# source_eagle.net
KiCad netlist of a schematic drawn in EAGLE
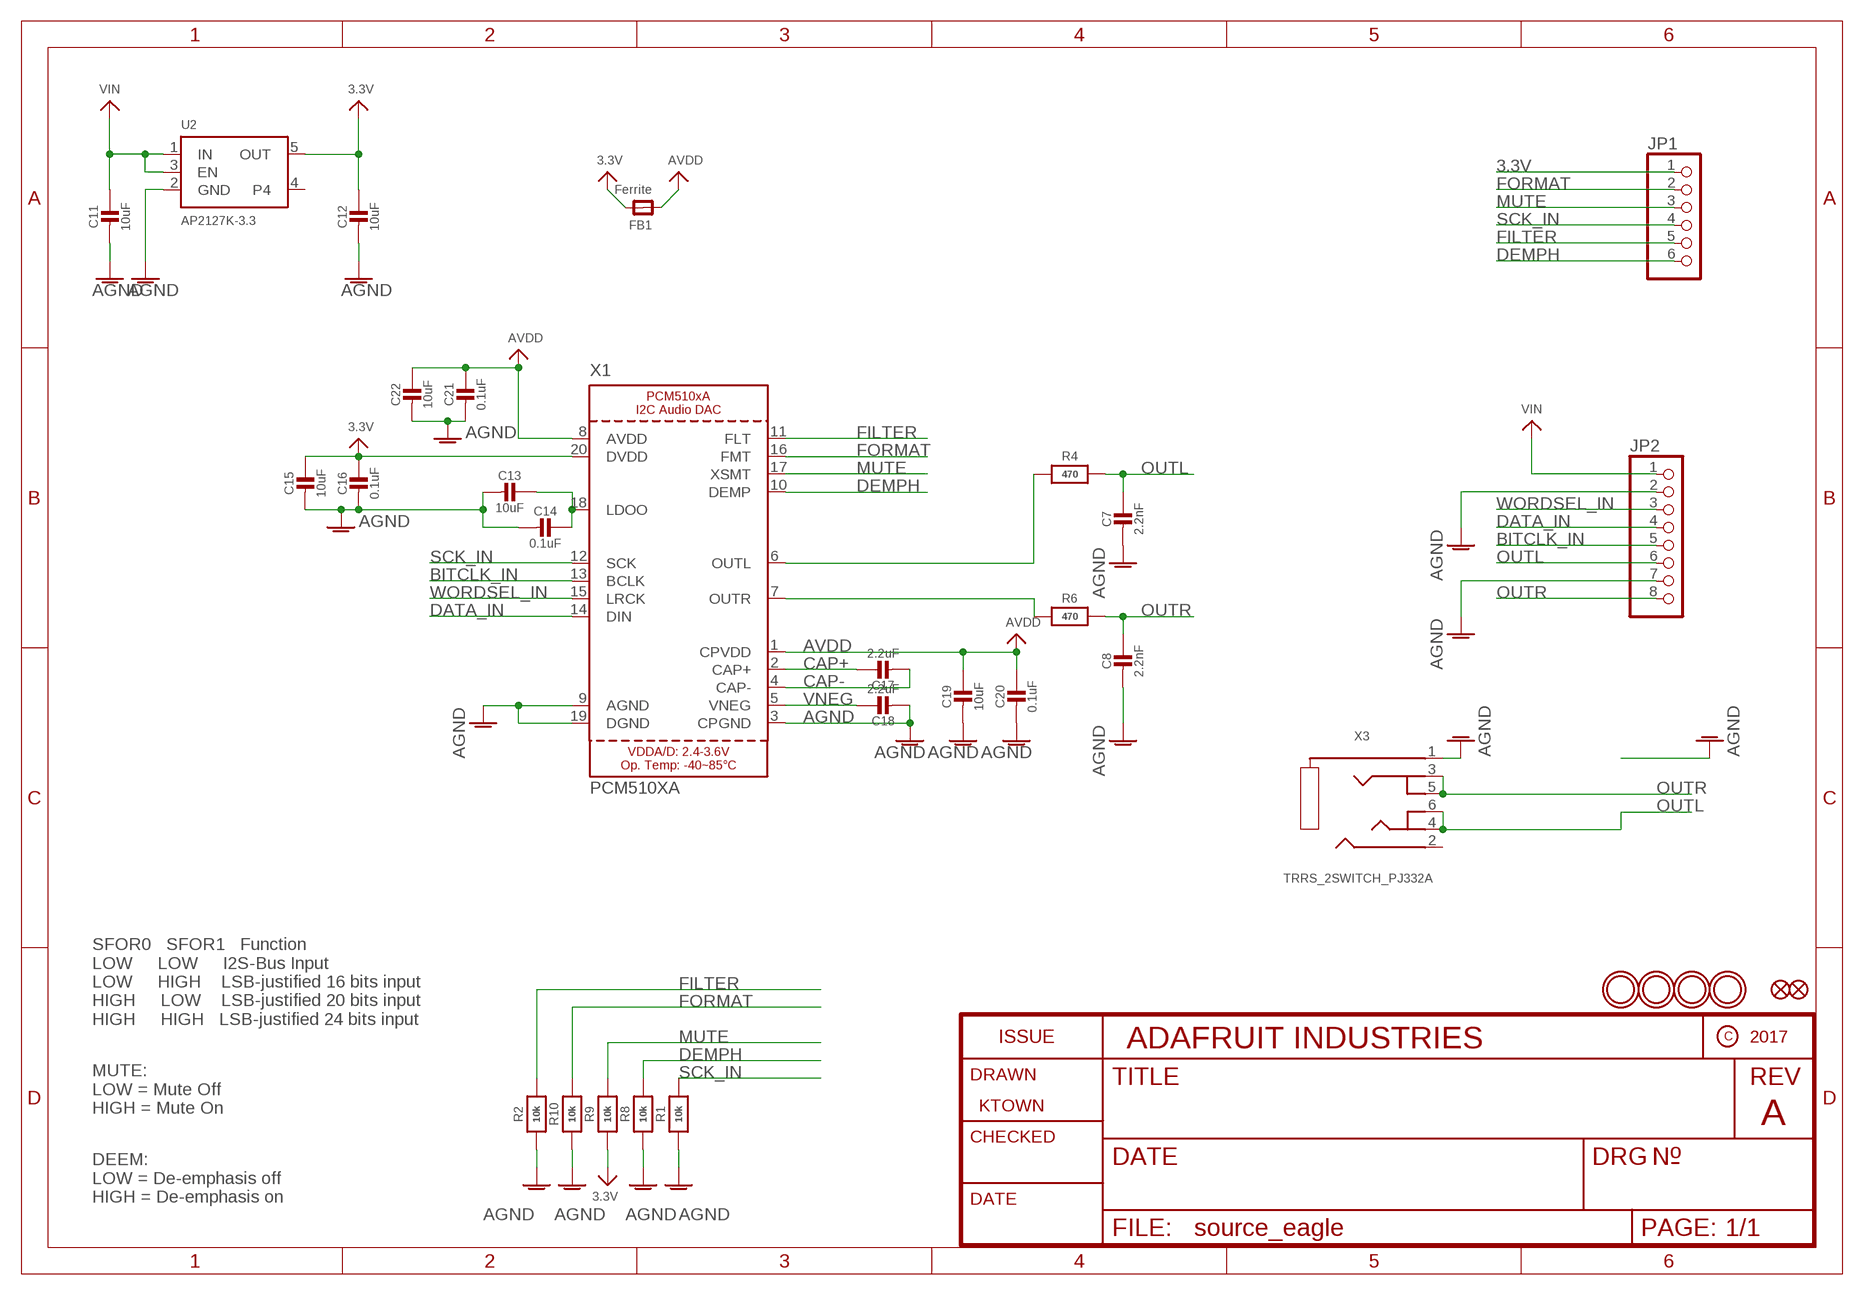
[diagram p0: schematic, sheet 1]

(export (version "E")
  (design (tool "Eeschema 10.0.6"))
  (components
    (comp (ref "C7")
      (value "2.2nF")
      (footprint "eagle-import:0603-NO")
      (libsource (lib "eagle-import") (part "CAP_CERAMIC0603_NO"))
    )
    (comp (ref "C8")
      (value "2.2nF")
      (footprint "eagle-import:0603-NO")
      (libsource (lib "eagle-import") (part "CAP_CERAMIC0603_NO"))
    )
    (comp (ref "C11")
      (value "10uF")
      (footprint "eagle-import:0805-NO")
      (libsource (lib "eagle-import") (part "CAP_CERAMIC0805-NOOUTLINE"))
    )
    (comp (ref "C12")
      (value "10uF")
      (footprint "eagle-import:0805-NO")
      (libsource (lib "eagle-import") (part "CAP_CERAMIC0805-NOOUTLINE"))
    )
    (comp (ref "C13")
      (value "10uF")
      (footprint "eagle-import:0805-NO")
      (libsource (lib "eagle-import") (part "CAP_CERAMIC0805-NOOUTLINE"))
    )
    (comp (ref "C14")
      (value "0.1uF")
      (footprint "eagle-import:0603-NO")
      (libsource (lib "eagle-import") (part "CAP_CERAMIC0603_NO"))
    )
    (comp (ref "C15")
      (value "10uF")
      (footprint "eagle-import:0805-NO")
      (libsource (lib "eagle-import") (part "CAP_CERAMIC0805-NOOUTLINE"))
    )
    (comp (ref "C16")
      (value "0.1uF")
      (footprint "eagle-import:0603-NO")
      (libsource (lib "eagle-import") (part "CAP_CERAMIC0603_NO"))
    )
    (comp (ref "C17")
      (value "2.2uF")
      (footprint "eagle-import:0603-NO")
      (libsource (lib "eagle-import") (part "CAP_CERAMIC0603_NO"))
    )
    (comp (ref "C18")
      (value "2.2uF")
      (footprint "eagle-import:0603-NO")
      (libsource (lib "eagle-import") (part "CAP_CERAMIC0603_NO"))
    )
    (comp (ref "C19")
      (value "10uF")
      (footprint "eagle-import:0805-NO")
      (libsource (lib "eagle-import") (part "CAP_CERAMIC0805-NOOUTLINE"))
    )
    (comp (ref "C20")
      (value "0.1uF")
      (footprint "eagle-import:0603-NO")
      (libsource (lib "eagle-import") (part "CAP_CERAMIC0603_NO"))
    )
    (comp (ref "C21")
      (value "0.1uF")
      (footprint "eagle-import:0603-NO")
      (libsource (lib "eagle-import") (part "CAP_CERAMIC0603_NO"))
    )
    (comp (ref "C22")
      (value "10uF")
      (footprint "eagle-import:0805-NO")
      (libsource (lib "eagle-import") (part "CAP_CERAMIC0805-NOOUTLINE"))
    )
    (comp (ref "FB1")
      (value "Ferrite")
      (footprint "eagle-import:0603-NO")
      (libsource (lib "eagle-import") (part "FERRITE-0603NO"))
    )
    (comp (ref "FID1")
      (value "FIDUCIAL_0.5MM")
      (footprint "eagle-import:FIDUCIAL_0.5MM")
      (libsource (lib "eagle-import") (part "FIDUCIAL_0.5MM"))
    )
    (comp (ref "FID2")
      (value "FIDUCIAL_0.5MM")
      (footprint "eagle-import:FIDUCIAL_0.5MM")
      (libsource (lib "eagle-import") (part "FIDUCIAL_0.5MM"))
    )
    (comp (ref "JP1")
      (value "HEADER-1X670MIL")
      (footprint "eagle-import:1X06_ROUND_70")
      (libsource (lib "eagle-import") (part "HEADER-1X670MIL"))
    )
    (comp (ref "JP2")
      (value "HEADER-1X8ROUND")
      (footprint "eagle-import:1X08_ROUND")
      (libsource (lib "eagle-import") (part "HEADER-1X8ROUND"))
    )
    (comp (ref "R1")
      (value "10k")
      (footprint "eagle-import:0603-NO")
      (libsource (lib "eagle-import") (part "RESISTOR_0603_NOOUT"))
    )
    (comp (ref "R2")
      (value "10k")
      (footprint "eagle-import:0603-NO")
      (libsource (lib "eagle-import") (part "RESISTOR_0603_NOOUT"))
    )
    (comp (ref "R4")
      (value "470")
      (footprint "eagle-import:0603-NO")
      (libsource (lib "eagle-import") (part "RESISTOR_0603_NOOUT"))
    )
    (comp (ref "R6")
      (value "470")
      (footprint "eagle-import:0603-NO")
      (libsource (lib "eagle-import") (part "RESISTOR_0603_NOOUT"))
    )
    (comp (ref "R8")
      (value "10k")
      (footprint "eagle-import:0603-NO")
      (libsource (lib "eagle-import") (part "RESISTOR_0603_NOOUT"))
    )
    (comp (ref "R9")
      (value "10k")
      (footprint "eagle-import:0603-NO")
      (libsource (lib "eagle-import") (part "RESISTOR_0603_NOOUT"))
    )
    (comp (ref "R10")
      (value "10k")
      (footprint "eagle-import:0603-NO")
      (libsource (lib "eagle-import") (part "RESISTOR_0603_NOOUT"))
    )
    (comp (ref "U$11")
      (value "MOUNTINGHOLE2.5")
      (footprint "eagle-import:MOUNTINGHOLE_2.5_PLATED")
      (libsource (lib "eagle-import") (part "MOUNTINGHOLE2.5"))
    )
    (comp (ref "U$12")
      (value "MOUNTINGHOLE2.5")
      (footprint "eagle-import:MOUNTINGHOLE_2.5_PLATED")
      (libsource (lib "eagle-import") (part "MOUNTINGHOLE2.5"))
    )
    (comp (ref "U$13")
      (value "MOUNTINGHOLE2.5")
      (footprint "eagle-import:MOUNTINGHOLE_2.5_PLATED")
      (libsource (lib "eagle-import") (part "MOUNTINGHOLE2.5"))
    )
    (comp (ref "U$14")
      (value "MOUNTINGHOLE2.5")
      (footprint "eagle-import:MOUNTINGHOLE_2.5_PLATED")
      (libsource (lib "eagle-import") (part "MOUNTINGHOLE2.5"))
    )
    (comp (ref "U2")
      (value "AP2127K-3.3")
      (footprint "eagle-import:SOT23-5")
      (libsource (lib "eagle-import") (part "VREG_SOT23-5"))
    )
    (comp (ref "X1")
      (value "PCM510XA")
      (footprint "eagle-import:TSSOP20")
      (libsource (lib "eagle-import") (part "PCM510XA"))
    )
    (comp (ref "X3")
      (value "TRRS_2SWITCH_PJ332A")
      (footprint "eagle-import:PJ-332A")
      (libsource (lib "eagle-import") (part "TRRS_2SWITCH_PJ332A"))
    )
  )
  (nets
    (net (code "1") (name "/BITCLK_IN") (class "Default")
      (node (ref "JP2") (pin "5") (pinfunction "5_5") (pintype "passive"))
      (node (ref "X1") (pin "13") (pinfunction "BCLK_13") (pintype "input"))
    )
    (net (code "2") (name "/CAP+") (class "Default")
      (node (ref "C17") (pin "1") (pinfunction "1_1") (pintype "passive"))
      (node (ref "X1") (pin "2") (pinfunction "CAP+_2") (pintype "output"))
    )
    (net (code "3") (name "/CAP-") (class "Default")
      (node (ref "C17") (pin "2") (pinfunction "2_2") (pintype "passive"))
      (node (ref "X1") (pin "4") (pinfunction "CAP-_4") (pintype "output"))
    )
    (net (code "4") (name "/DATA_IN") (class "Default")
      (node (ref "JP2") (pin "4") (pinfunction "4_4") (pintype "passive"))
      (node (ref "X1") (pin "14") (pinfunction "DIN_14") (pintype "input"))
    )
    (net (code "5") (name "/DEMPH") (class "Default")
      (node (ref "JP1") (pin "6") (pinfunction "6_6") (pintype "passive"))
      (node (ref "R8") (pin "2") (pinfunction "2_2") (pintype "passive"))
      (node (ref "X1") (pin "10") (pinfunction "DEMP_10") (pintype "bidirectional"))
    )
    (net (code "6") (name "/FILTER") (class "Default")
      (node (ref "JP1") (pin "5") (pinfunction "5_5") (pintype "passive"))
      (node (ref "R2") (pin "2") (pinfunction "2_2") (pintype "passive"))
      (node (ref "X1") (pin "11") (pinfunction "FLT_11") (pintype "input"))
    )
    (net (code "7") (name "/FORMAT") (class "Default")
      (node (ref "JP1") (pin "2") (pinfunction "2_2") (pintype "passive"))
      (node (ref "R10") (pin "2") (pinfunction "2_2") (pintype "passive"))
      (node (ref "X1") (pin "16") (pinfunction "FMT_16") (pintype "input"))
    )
    (net (code "8") (name "/MUTE") (class "Default")
      (node (ref "JP1") (pin "3") (pinfunction "3_3") (pintype "passive"))
      (node (ref "R9") (pin "2") (pinfunction "2_2") (pintype "passive"))
      (node (ref "X1") (pin "17") (pinfunction "XSMT_17") (pintype "input"))
    )
    (net (code "9") (name "/OUTL") (class "Default")
      (node (ref "C7") (pin "1") (pinfunction "1_1") (pintype "passive"))
      (node (ref "JP2") (pin "6") (pinfunction "6_6") (pintype "passive"))
      (node (ref "R4") (pin "2") (pinfunction "2_2") (pintype "passive"))
      (node (ref "X3") (pin "4") (pinfunction "TIP_4") (pintype "passive"))
      (node (ref "X3") (pin "6") (pinfunction "TIP_SW_6") (pintype "passive"))
    )
    (net (code "10") (name "/OUTR") (class "Default")
      (node (ref "C8") (pin "1") (pinfunction "1_1") (pintype "passive"))
      (node (ref "JP2") (pin "8") (pinfunction "8_8") (pintype "passive"))
      (node (ref "R6") (pin "2") (pinfunction "2_2") (pintype "passive"))
      (node (ref "X3") (pin "3") (pinfunction "RING2_3") (pintype "passive"))
      (node (ref "X3") (pin "5") (pinfunction "R2_SW_5") (pintype "passive"))
    )
    (net (code "11") (name "/SCK_IN") (class "Default")
      (node (ref "JP1") (pin "4") (pinfunction "4_4") (pintype "passive"))
      (node (ref "R1") (pin "2") (pinfunction "2_2") (pintype "passive"))
      (node (ref "X1") (pin "12") (pinfunction "SCK_12") (pintype "input"))
    )
    (net (code "12") (name "/VNEG") (class "Default")
      (node (ref "C18") (pin "1") (pinfunction "1_1") (pintype "passive"))
      (node (ref "X1") (pin "5") (pinfunction "VNEG_5") (pintype "output"))
    )
    (net (code "13") (name "/WORDSEL_IN") (class "Default")
      (node (ref "JP2") (pin "3") (pinfunction "3_3") (pintype "passive"))
      (node (ref "X1") (pin "15") (pinfunction "LRCK_15") (pintype "input"))
    )
    (net (code "14") (name "3.3V") (class "Default")
      (node (ref "C12") (pin "1") (pinfunction "1_1") (pintype "passive"))
      (node (ref "C15") (pin "1") (pinfunction "1_1") (pintype "passive"))
      (node (ref "C16") (pin "1") (pinfunction "1_1") (pintype "passive"))
      (node (ref "FB1") (pin "2") (pinfunction "P$2_2") (pintype "passive"))
      (node (ref "JP1") (pin "1") (pinfunction "1_1") (pintype "passive"))
      (node (ref "R9") (pin "1") (pinfunction "1_1") (pintype "passive"))
      (node (ref "U2") (pin "5") (pinfunction "OUT_5") (pintype "power_in"))
      (node (ref "X1") (pin "20") (pinfunction "DVDD_20") (pintype "power_in"))
    )
    (net (code "15") (name "AGND") (class "Default")
      (node (ref "C11") (pin "2") (pinfunction "2_2") (pintype "passive"))
      (node (ref "C12") (pin "2") (pinfunction "2_2") (pintype "passive"))
      (node (ref "C13") (pin "2") (pinfunction "2_2") (pintype "passive"))
      (node (ref "C14") (pin "2") (pinfunction "2_2") (pintype "passive"))
      (node (ref "C15") (pin "2") (pinfunction "2_2") (pintype "passive"))
      (node (ref "C16") (pin "2") (pinfunction "2_2") (pintype "passive"))
      (node (ref "C18") (pin "2") (pinfunction "2_2") (pintype "passive"))
      (node (ref "C19") (pin "2") (pinfunction "2_2") (pintype "passive"))
      (node (ref "C20") (pin "2") (pinfunction "2_2") (pintype "passive"))
      (node (ref "C21") (pin "2") (pinfunction "2_2") (pintype "passive"))
      (node (ref "C22") (pin "2") (pinfunction "2_2") (pintype "passive"))
      (node (ref "C7") (pin "2") (pinfunction "2_2") (pintype "passive"))
      (node (ref "C8") (pin "2") (pinfunction "2_2") (pintype "passive"))
      (node (ref "JP2") (pin "2") (pinfunction "2_2") (pintype "passive"))
      (node (ref "JP2") (pin "7") (pinfunction "7_7") (pintype "passive"))
      (node (ref "R1") (pin "1") (pinfunction "1_1") (pintype "passive"))
      (node (ref "R10") (pin "1") (pinfunction "1_1") (pintype "passive"))
      (node (ref "R2") (pin "1") (pinfunction "1_1") (pintype "passive"))
      (node (ref "R8") (pin "1") (pinfunction "1_1") (pintype "passive"))
      (node (ref "U2") (pin "2") (pinfunction "GND_2") (pintype "power_in"))
      (node (ref "X1") (pin "19") (pinfunction "DGND_19") (pintype "power_in"))
      (node (ref "X1") (pin "3") (pinfunction "CPGND_3") (pintype "power_in"))
      (node (ref "X1") (pin "9") (pinfunction "AGND_9") (pintype "power_in"))
      (node (ref "X3") (pin "1") (pinfunction "RING_1") (pintype "passive"))
    )
    (net (code "16") (name "AVDD") (class "Default")
      (node (ref "C19") (pin "1") (pinfunction "1_1") (pintype "passive"))
      (node (ref "C20") (pin "1") (pinfunction "1_1") (pintype "passive"))
      (node (ref "C21") (pin "1") (pinfunction "1_1") (pintype "passive"))
      (node (ref "C22") (pin "1") (pinfunction "1_1") (pintype "passive"))
      (node (ref "FB1") (pin "1") (pinfunction "P$1_1") (pintype "passive"))
      (node (ref "X1") (pin "1") (pinfunction "CPVDD_1") (pintype "power_in"))
      (node (ref "X1") (pin "8") (pinfunction "AVDD_8") (pintype "power_in"))
    )
    (net (code "17") (name "Net-(X1-LDOO)") (class "Default")
      (node (ref "C13") (pin "1") (pinfunction "1_1") (pintype "passive"))
      (node (ref "C14") (pin "1") (pinfunction "1_1") (pintype "passive"))
      (node (ref "X1") (pin "18") (pinfunction "LDOO_18") (pintype "input"))
    )
    (net (code "18") (name "Net-(X1-OUTL)") (class "Default")
      (node (ref "R4") (pin "1") (pinfunction "1_1") (pintype "passive"))
      (node (ref "X1") (pin "6") (pinfunction "OUTL_6") (pintype "output"))
    )
    (net (code "19") (name "Net-(X1-OUTR)") (class "Default")
      (node (ref "R6") (pin "1") (pinfunction "1_1") (pintype "passive"))
      (node (ref "X1") (pin "7") (pinfunction "OUTR_7") (pintype "output"))
    )
    (net (code "20") (name "VIN") (class "Default")
      (node (ref "C11") (pin "1") (pinfunction "1_1") (pintype "passive"))
      (node (ref "JP2") (pin "1") (pinfunction "1_1") (pintype "passive"))
      (node (ref "U2") (pin "1") (pinfunction "IN_1") (pintype "power_in"))
      (node (ref "U2") (pin "3") (pinfunction "EN_3") (pintype "input"))
    )
    (net (code "21") (name "unconnected-(U2-P4-Pad4)") (class "Default")
      (node (ref "U2") (pin "4") (pinfunction "P4_4") (pintype "bidirectional"))
    )
    (net (code "22") (name "unconnected-(X3-RING1-Pad2)") (class "Default")
      (node (ref "X3") (pin "2") (pinfunction "RING1_2") (pintype "passive"))
    )
  )
)
